# power.net
KiCad netlist of a schematic drawn in Altium Designer
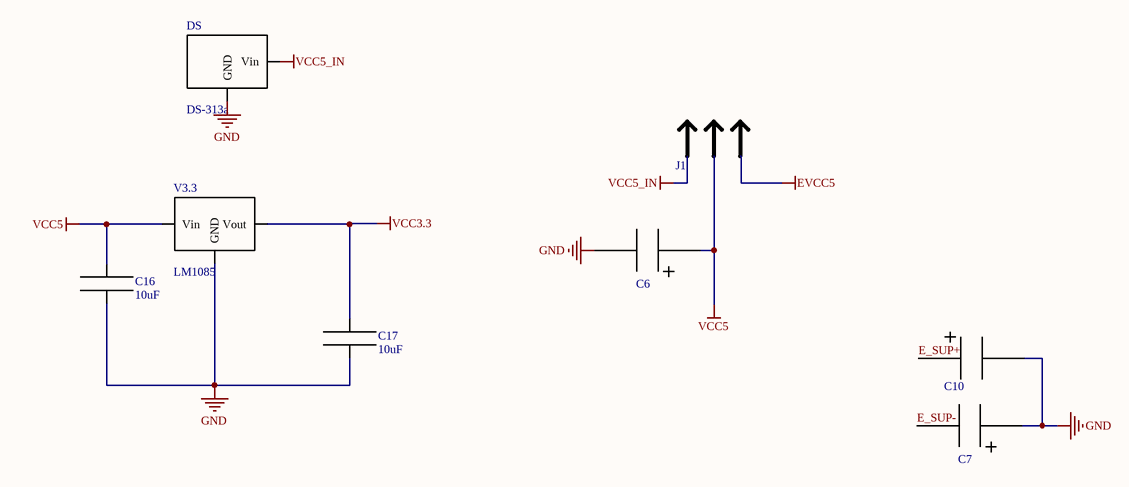
[diagram p0: power.SchDoc]

(export (version "E")
  (design (tool "Eeschema 10.0.6"))
  (components
    (comp (ref "C6")
      (value "C_Ta")
      (footprint "C_Ta")
      (description "tantalum capacitor")
      (libsource (lib "elvis_lib") (part "C_Ta"))
    )
    (comp (ref "C7")
      (value "C_Ta")
      (footprint "C_Ta")
      (description "tantalum capacitor")
      (libsource (lib "elvis_lib") (part "C_Ta"))
    )
    (comp (ref "C10")
      (value "C_Ta")
      (footprint "C_Ta")
      (description "tantalum capacitor")
      (libsource (lib "elvis_lib") (part "C_Ta"))
    )
    (comp (ref "C16")
      (value "10uF")
      (footprint "elvis_lib:R0805")
      (libsource (lib "elvis_lib") (part "CAPACITY"))
    )
    (comp (ref "C17")
      (value "10uF")
      (footprint "elvis_lib:R0805")
      (libsource (lib "elvis_lib") (part "CAPACITY"))
    )
    (comp (ref "DS")
      (value "DS-313a")
      (footprint "elvis_lib:ds-313")
      (libsource (lib "elvis_lib") (part "DS-313a"))
    )
    (comp (ref "J1")
      (value "JUMPER_SWITCH_2S")
      (footprint "JUMPER_SWITCH_2S")
      (description "2 state jumper switch")
      (libsource (lib "elvis_lib") (part "JUMPER_SWITCH_2S"))
    )
    (comp (ref "V3.3")
      (value "LM1085")
      (footprint "elvis_lib:LM1085")
      (libsource (lib "elvis_lib") (part "LM1085"))
    )
  )
  (nets
    (net (code "1") (name "/E_SUP+") (class "Default")
      (node (ref "C10") (pin "1") (pinfunction "1_1") (pintype "passive"))
    )
    (net (code "2") (name "/E_SUP-") (class "Default")
      (node (ref "C7") (pin "2") (pinfunction "2_2") (pintype "passive"))
    )
    (net (code "3") (name "EVCC5") (class "Default")
      (node (ref "J1") (pin "2") (pinfunction "2_2") (pintype "passive"))
    )
    (net (code "4") (name "GND") (class "Default")
      (node (ref "C10") (pin "2") (pinfunction "2_2") (pintype "passive"))
      (node (ref "C16") (pin "2") (pinfunction "2_2") (pintype "passive"))
      (node (ref "C17") (pin "2") (pinfunction "2_2") (pintype "passive"))
      (node (ref "C6") (pin "2") (pinfunction "2_2") (pintype "passive"))
      (node (ref "C7") (pin "1") (pinfunction "1_1") (pintype "passive"))
      (node (ref "DS") (pin "0") (pinfunction "GND_0") (pintype "passive"))
      (node (ref "V3.3") (pin "0") (pinfunction "GND_0") (pintype "passive"))
    )
    (net (code "5") (name "VCC3.3") (class "Default")
      (node (ref "C17") (pin "1") (pinfunction "1_1") (pintype "passive"))
      (node (ref "V3.3") (pin "1") (pinfunction "Vout_1") (pintype "passive"))
    )
    (net (code "6") (name "VCC5") (class "Default")
      (node (ref "C16") (pin "1") (pinfunction "1_1") (pintype "passive"))
      (node (ref "C6") (pin "1") (pinfunction "1_1") (pintype "passive"))
      (node (ref "J1") (pin "0") (pinfunction "0_0") (pintype "passive"))
      (node (ref "V3.3") (pin "2") (pinfunction "Vin_2") (pintype "passive"))
    )
    (net (code "7") (name "VCC5_IN") (class "Default")
      (node (ref "DS") (pin "1") (pinfunction "Vin_1") (pintype "passive"))
      (node (ref "J1") (pin "1") (pinfunction "1_1") (pintype "passive"))
    )
  )
)
